# control.net
KiCad netlist of a schematic drawn in EAGLE
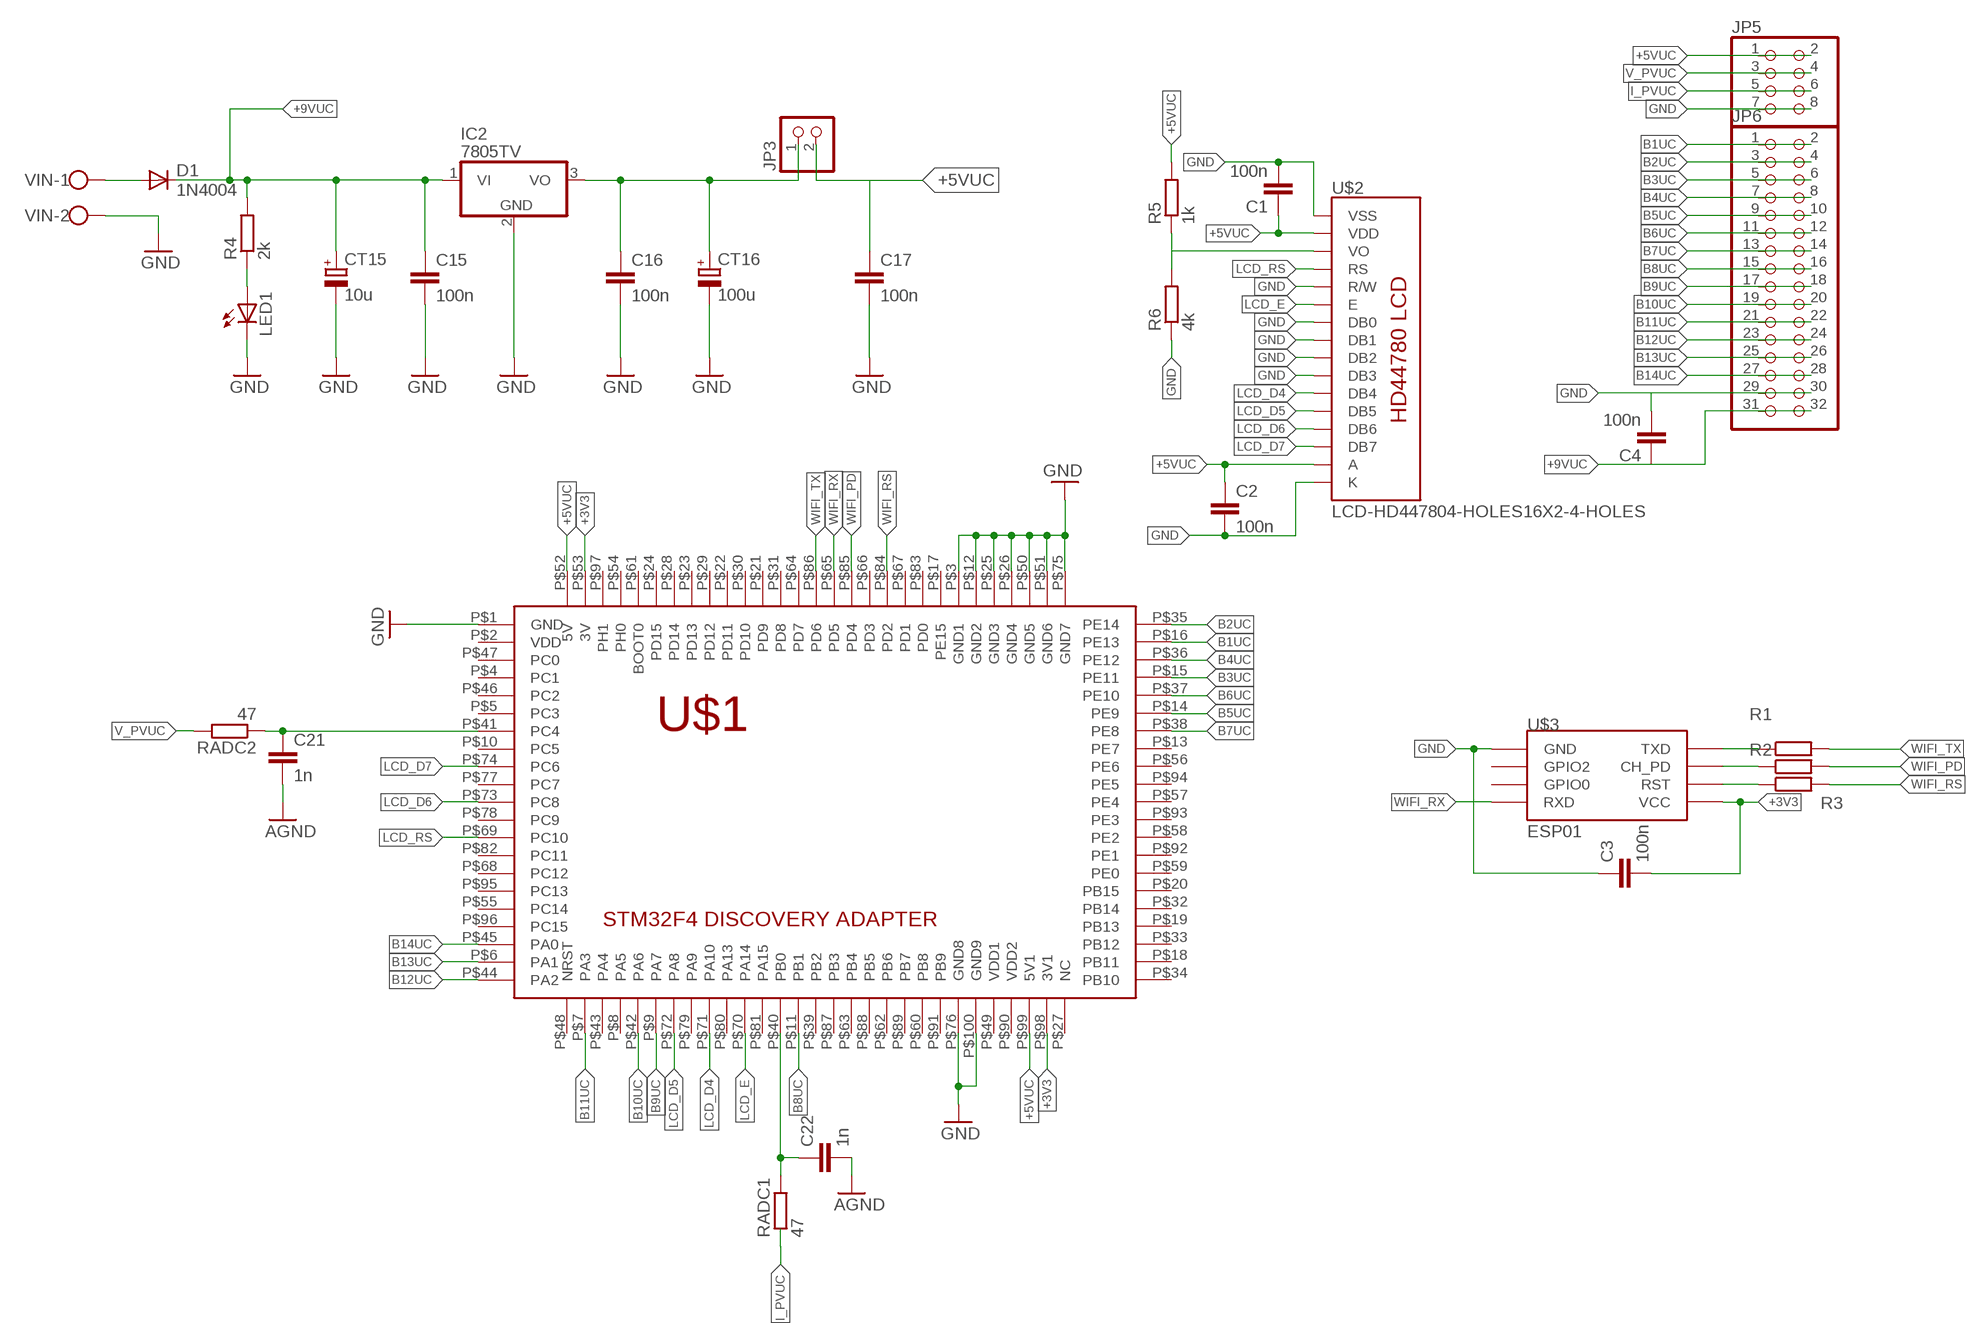
[diagram p0: schematic, sheet 1]

(export (version "E")
  (design (tool "Eeschema 10.0.6"))
  (components
    (comp (ref "C1")
      (value "100n")
      (footprint "eagle-import:C1206")
      (libsource (lib "eagle-import") (part "C-EUC1206"))
    )
    (comp (ref "C2")
      (value "100n")
      (footprint "eagle-import:C1206")
      (libsource (lib "eagle-import") (part "C-EUC1206"))
    )
    (comp (ref "C3")
      (value "100n")
      (footprint "eagle-import:C1206")
      (libsource (lib "eagle-import") (part "C-EUC1206"))
    )
    (comp (ref "C4")
      (value "100n")
      (footprint "eagle-import:C1206")
      (libsource (lib "eagle-import") (part "C-EUC1206"))
    )
    (comp (ref "C15")
      (value "100n")
      (footprint "eagle-import:C1206")
      (libsource (lib "eagle-import") (part "C-EUC1206"))
    )
    (comp (ref "C16")
      (value "100n")
      (footprint "eagle-import:C1206")
      (libsource (lib "eagle-import") (part "C-EUC1206"))
    )
    (comp (ref "C17")
      (value "100n")
      (footprint "eagle-import:C1206")
      (libsource (lib "eagle-import") (part "C-EUC1206"))
    )
    (comp (ref "C21")
      (value "1n")
      (footprint "eagle-import:C1206")
      (libsource (lib "eagle-import") (part "C-EUC1206"))
    )
    (comp (ref "C22")
      (value "1n")
      (footprint "eagle-import:C1206")
      (libsource (lib "eagle-import") (part "C-EUC1206"))
    )
    (comp (ref "CT15")
      (value "10u")
      (footprint "eagle-import:B_3528-21W")
      (libsource (lib "eagle-import") (part "CPOL-EUB/3528-21W"))
    )
    (comp (ref "CT16")
      (value "100u")
      (footprint "eagle-import:D_7343-31R")
      (libsource (lib "eagle-import") (part "CPOL-EUD/7343-31R"))
    )
    (comp (ref "D1")
      (value "1N4004")
      (footprint "eagle-import:DO214AC")
      (libsource (lib "eagle-import") (part "1N4004"))
    )
    (comp (ref "IC2")
      (value "7805TV")
      (footprint "eagle-import:TO220V")
      (libsource (lib "eagle-import") (part "78TV05"))
    )
    (comp (ref "JP3")
      (value "PINHD-1X2")
      (footprint "eagle-import:1X02")
      (libsource (lib "eagle-import") (part "PINHD-1X2"))
    )
    (comp (ref "JP5")
      (value "PINHD-2X4/90")
      (footprint "eagle-import:2X04_90")
      (libsource (lib "eagle-import") (part "PINHD-2X4/90"))
    )
    (comp (ref "JP6")
      (value "PINHD-2X16/90")
      (footprint "eagle-import:2X16_90")
      (libsource (lib "eagle-import") (part "PINHD-2X16/90"))
    )
    (comp (ref "LED1")
      (value "LEDCHIPLED_0805")
      (footprint "eagle-import:CHIPLED_0805")
      (libsource (lib "eagle-import") (part "LEDCHIPLED_0805"))
    )
    (comp (ref "R1")
      (value "R-EU_R0603")
      (footprint "eagle-import:R0603")
      (libsource (lib "eagle-import") (part "R-EU_R0603"))
    )
    (comp (ref "R2")
      (value "R-EU_R0603")
      (footprint "eagle-import:R0603")
      (libsource (lib "eagle-import") (part "R-EU_R0603"))
    )
    (comp (ref "R3")
      (value "R-EU_R0603")
      (footprint "eagle-import:R0603")
      (libsource (lib "eagle-import") (part "R-EU_R0603"))
    )
    (comp (ref "R4")
      (value "2k")
      (footprint "eagle-import:M1206")
      (libsource (lib "eagle-import") (part "R-EU_M1206"))
    )
    (comp (ref "R5")
      (value "1k")
      (footprint "eagle-import:M1206")
      (libsource (lib "eagle-import") (part "R-EU_M1206"))
    )
    (comp (ref "R6")
      (value "4k")
      (footprint "eagle-import:M1206")
      (libsource (lib "eagle-import") (part "R-EU_M1206"))
    )
    (comp (ref "RADC1")
      (value "47")
      (footprint "eagle-import:R1206")
      (libsource (lib "eagle-import") (part "R-EU_R1206"))
    )
    (comp (ref "RADC2")
      (value "47")
      (footprint "eagle-import:R1206")
      (libsource (lib "eagle-import") (part "R-EU_R1206"))
    )
    (comp (ref "U$1")
      (value "STM32F4ADAPTER")
      (footprint "eagle-import:DISCOVERYPACK")
      (libsource (lib "eagle-import") (part "STM32F4ADAPTER"))
    )
    (comp (ref "U$2")
      (value "LCD-HD447804-HOLES16X2-4-HOLES")
      (footprint "eagle-import:LCD-16X2-4HOLES")
      (libsource (lib "eagle-import") (part "LCD-HD4478016X2-4-HOLES4-HOLES"))
    )
    (comp (ref "U$3")
      (value "ESP01")
      (footprint "eagle-import:ESP01")
      (libsource (lib "eagle-import") (part "ESP01"))
    )
    (comp (ref "VIN")
      (value "W237-102")
      (footprint "eagle-import:W237-102")
      (fields (field (name "MPN") "237-102"))
      (libsource (lib "eagle-import") (part "W237-102"))
    )
  )
  (nets
    (net (code "1") (name "+3V3") (class "Default")
      (node (ref "C3") (pin "2") (pinfunction "2_2") (pintype "passive"))
      (node (ref "U$1") (pin "P$53") (pinfunction "3V_P$53") (pintype "bidirectional"))
      (node (ref "U$1") (pin "P$98") (pinfunction "3V1_P$98") (pintype "bidirectional"))
      (node (ref "U$3") (pin "VCC") (pinfunction "VCC_VCC") (pintype "bidirectional"))
    )
    (net (code "2") (name "+5VUC") (class "Default")
      (node (ref "C1") (pin "1") (pinfunction "1_1") (pintype "passive"))
      (node (ref "C17") (pin "1") (pinfunction "1_1") (pintype "passive"))
      (node (ref "C2") (pin "1") (pinfunction "1_1") (pintype "passive"))
      (node (ref "JP3") (pin "2") (pinfunction "2_2") (pintype "passive"))
      (node (ref "JP5") (pin "1") (pinfunction "1_1") (pintype "passive"))
      (node (ref "JP5") (pin "2") (pinfunction "2_2") (pintype "passive"))
      (node (ref "R5") (pin "2") (pinfunction "2_2") (pintype "passive"))
      (node (ref "U$1") (pin "P$52") (pinfunction "5V_P$52") (pintype "bidirectional"))
      (node (ref "U$1") (pin "P$99") (pinfunction "5V1_P$99") (pintype "bidirectional"))
      (node (ref "U$2") (pin "15") (pinfunction "A_15") (pintype "power_in"))
      (node (ref "U$2") (pin "2") (pinfunction "VDD_2") (pintype "power_in"))
    )
    (net (code "3") (name "+9VUC") (class "Default")
      (node (ref "C15") (pin "1") (pinfunction "1_1") (pintype "passive"))
      (node (ref "C4") (pin "1") (pinfunction "1_1") (pintype "passive"))
      (node (ref "CT15") (pin "+") (pinfunction "+_+") (pintype "passive"))
      (node (ref "D1") (pin "C") (pinfunction "C_C") (pintype "passive"))
      (node (ref "IC2") (pin "1") (pinfunction "VI_1") (pintype "input"))
      (node (ref "JP6") (pin "31") (pinfunction "31_31") (pintype "passive"))
      (node (ref "JP6") (pin "32") (pinfunction "32_32") (pintype "passive"))
      (node (ref "R4") (pin "2") (pinfunction "2_2") (pintype "passive"))
    )
    (net (code "4") (name "B1UC") (class "Default")
      (node (ref "JP6") (pin "1") (pinfunction "1_1") (pintype "passive"))
      (node (ref "JP6") (pin "2") (pinfunction "2_2") (pintype "passive"))
      (node (ref "U$1") (pin "P$16") (pinfunction "PE13_P$16") (pintype "bidirectional"))
    )
    (net (code "5") (name "B2UC") (class "Default")
      (node (ref "JP6") (pin "3") (pinfunction "3_3") (pintype "passive"))
      (node (ref "JP6") (pin "4") (pinfunction "4_4") (pintype "passive"))
      (node (ref "U$1") (pin "P$35") (pinfunction "PE14_P$35") (pintype "bidirectional"))
    )
    (net (code "6") (name "B3UC") (class "Default")
      (node (ref "JP6") (pin "5") (pinfunction "5_5") (pintype "passive"))
      (node (ref "JP6") (pin "6") (pinfunction "6_6") (pintype "passive"))
      (node (ref "U$1") (pin "P$15") (pinfunction "PE11_P$15") (pintype "bidirectional"))
    )
    (net (code "7") (name "B4UC") (class "Default")
      (node (ref "JP6") (pin "7") (pinfunction "7_7") (pintype "passive"))
      (node (ref "JP6") (pin "8") (pinfunction "8_8") (pintype "passive"))
      (node (ref "U$1") (pin "P$36") (pinfunction "PE12_P$36") (pintype "bidirectional"))
    )
    (net (code "8") (name "B5UC") (class "Default")
      (node (ref "JP6") (pin "10") (pinfunction "10_10") (pintype "passive"))
      (node (ref "JP6") (pin "9") (pinfunction "9_9") (pintype "passive"))
      (node (ref "U$1") (pin "P$14") (pinfunction "PE9_P$14") (pintype "bidirectional"))
    )
    (net (code "9") (name "B6UC") (class "Default")
      (node (ref "JP6") (pin "11") (pinfunction "11_11") (pintype "passive"))
      (node (ref "JP6") (pin "12") (pinfunction "12_12") (pintype "passive"))
      (node (ref "U$1") (pin "P$37") (pinfunction "PE10_P$37") (pintype "bidirectional"))
    )
    (net (code "10") (name "B7UC") (class "Default")
      (node (ref "JP6") (pin "13") (pinfunction "13_13") (pintype "passive"))
      (node (ref "JP6") (pin "14") (pinfunction "14_14") (pintype "passive"))
      (node (ref "U$1") (pin "P$38") (pinfunction "PE8_P$38") (pintype "bidirectional"))
    )
    (net (code "11") (name "B8UC") (class "Default")
      (node (ref "JP6") (pin "15") (pinfunction "15_15") (pintype "passive"))
      (node (ref "JP6") (pin "16") (pinfunction "16_16") (pintype "passive"))
      (node (ref "U$1") (pin "P$11") (pinfunction "PB1_P$11") (pintype "bidirectional"))
    )
    (net (code "12") (name "B9UC") (class "Default")
      (node (ref "JP6") (pin "17") (pinfunction "17_17") (pintype "passive"))
      (node (ref "JP6") (pin "18") (pinfunction "18_18") (pintype "passive"))
      (node (ref "U$1") (pin "P$9") (pinfunction "PA7_P$9") (pintype "bidirectional"))
    )
    (net (code "13") (name "B10UC") (class "Default")
      (node (ref "JP6") (pin "19") (pinfunction "19_19") (pintype "passive"))
      (node (ref "JP6") (pin "20") (pinfunction "20_20") (pintype "passive"))
      (node (ref "U$1") (pin "P$42") (pinfunction "PA6_P$42") (pintype "bidirectional"))
    )
    (net (code "14") (name "B11UC") (class "Default")
      (node (ref "JP6") (pin "21") (pinfunction "21_21") (pintype "passive"))
      (node (ref "JP6") (pin "22") (pinfunction "22_22") (pintype "passive"))
      (node (ref "U$1") (pin "P$7") (pinfunction "PA3_P$7") (pintype "bidirectional"))
    )
    (net (code "15") (name "B12UC") (class "Default")
      (node (ref "JP6") (pin "23") (pinfunction "23_23") (pintype "passive"))
      (node (ref "JP6") (pin "24") (pinfunction "24_24") (pintype "passive"))
      (node (ref "U$1") (pin "P$44") (pinfunction "PA2_P$44") (pintype "bidirectional"))
    )
    (net (code "16") (name "B13UC") (class "Default")
      (node (ref "JP6") (pin "25") (pinfunction "25_25") (pintype "passive"))
      (node (ref "JP6") (pin "26") (pinfunction "26_26") (pintype "passive"))
      (node (ref "U$1") (pin "P$6") (pinfunction "PA1_P$6") (pintype "bidirectional"))
    )
    (net (code "17") (name "B14UC") (class "Default")
      (node (ref "JP6") (pin "27") (pinfunction "27_27") (pintype "passive"))
      (node (ref "JP6") (pin "28") (pinfunction "28_28") (pintype "passive"))
      (node (ref "U$1") (pin "P$45") (pinfunction "PA0_P$45") (pintype "bidirectional"))
    )
    (net (code "18") (name "GND") (class "Default")
      (node (ref "C1") (pin "2") (pinfunction "2_2") (pintype "passive"))
      (node (ref "C15") (pin "2") (pinfunction "2_2") (pintype "passive"))
      (node (ref "C16") (pin "2") (pinfunction "2_2") (pintype "passive"))
      (node (ref "C17") (pin "2") (pinfunction "2_2") (pintype "passive"))
      (node (ref "C2") (pin "2") (pinfunction "2_2") (pintype "passive"))
      (node (ref "C21") (pin "2") (pinfunction "2_2") (pintype "passive"))
      (node (ref "C22") (pin "2") (pinfunction "2_2") (pintype "passive"))
      (node (ref "C3") (pin "1") (pinfunction "1_1") (pintype "passive"))
      (node (ref "C4") (pin "2") (pinfunction "2_2") (pintype "passive"))
      (node (ref "CT15") (pin "-") (pinfunction "-_-") (pintype "passive"))
      (node (ref "CT16") (pin "-") (pinfunction "-_-") (pintype "passive"))
      (node (ref "IC2") (pin "2") (pinfunction "GND_2") (pintype "passive"))
      (node (ref "JP5") (pin "7") (pinfunction "7_7") (pintype "passive"))
      (node (ref "JP5") (pin "8") (pinfunction "8_8") (pintype "passive"))
      (node (ref "JP6") (pin "29") (pinfunction "29_29") (pintype "passive"))
      (node (ref "JP6") (pin "30") (pinfunction "30_30") (pintype "passive"))
      (node (ref "LED1") (pin "C") (pinfunction "C_C") (pintype "passive"))
      (node (ref "R6") (pin "1") (pinfunction "1_1") (pintype "passive"))
      (node (ref "U$1") (pin "P$1") (pinfunction "GND_P$1") (pintype "bidirectional"))
      (node (ref "U$1") (pin "P$100") (pinfunction "GND9_P$100") (pintype "bidirectional"))
      (node (ref "U$1") (pin "P$12") (pinfunction "GND2_P$12") (pintype "bidirectional"))
      (node (ref "U$1") (pin "P$25") (pinfunction "GND3_P$25") (pintype "bidirectional"))
      (node (ref "U$1") (pin "P$26") (pinfunction "GND4_P$26") (pintype "bidirectional"))
      (node (ref "U$1") (pin "P$3") (pinfunction "GND1_P$3") (pintype "bidirectional"))
      (node (ref "U$1") (pin "P$50") (pinfunction "GND5_P$50") (pintype "bidirectional"))
      (node (ref "U$1") (pin "P$51") (pinfunction "GND6_P$51") (pintype "bidirectional"))
      (node (ref "U$1") (pin "P$75") (pinfunction "GND7_P$75") (pintype "bidirectional"))
      (node (ref "U$1") (pin "P$76") (pinfunction "GND8_P$76") (pintype "bidirectional"))
      (node (ref "U$2") (pin "1") (pinfunction "VSS_1") (pintype "power_in"))
      (node (ref "U$2") (pin "10") (pinfunction "DB3_10") (pintype "bidirectional"))
      (node (ref "U$2") (pin "16") (pinfunction "K_16") (pintype "power_in"))
      (node (ref "U$2") (pin "5") (pinfunction "R/W_5") (pintype "input"))
      (node (ref "U$2") (pin "7") (pinfunction "DB0_7") (pintype "bidirectional"))
      (node (ref "U$2") (pin "8") (pinfunction "DB1_8") (pintype "bidirectional"))
      (node (ref "U$2") (pin "9") (pinfunction "DB2_9") (pintype "bidirectional"))
      (node (ref "U$3") (pin "GND") (pinfunction "GND_GND") (pintype "bidirectional"))
      (node (ref "VIN") (pin "2") (pinfunction "KL_2") (pintype "passive"))
    )
    (net (code "19") (name "I_PVUC") (class "Default")
      (node (ref "JP5") (pin "5") (pinfunction "5_5") (pintype "passive"))
      (node (ref "JP5") (pin "6") (pinfunction "6_6") (pintype "passive"))
      (node (ref "RADC1") (pin "1") (pinfunction "1_1") (pintype "passive"))
    )
    (net (code "20") (name "LCD_D4") (class "Default")
      (node (ref "U$1") (pin "P$71") (pinfunction "PA10_P$71") (pintype "bidirectional"))
      (node (ref "U$2") (pin "11") (pinfunction "DB4_11") (pintype "bidirectional"))
    )
    (net (code "21") (name "LCD_D5") (class "Default")
      (node (ref "U$1") (pin "P$72") (pinfunction "PA8_P$72") (pintype "bidirectional"))
      (node (ref "U$2") (pin "12") (pinfunction "DB5_12") (pintype "bidirectional"))
    )
    (net (code "22") (name "LCD_D6") (class "Default")
      (node (ref "U$1") (pin "P$73") (pinfunction "PC8_P$73") (pintype "bidirectional"))
      (node (ref "U$2") (pin "13") (pinfunction "DB6_13") (pintype "bidirectional"))
    )
    (net (code "23") (name "LCD_D7") (class "Default")
      (node (ref "U$1") (pin "P$74") (pinfunction "PC6_P$74") (pintype "bidirectional"))
      (node (ref "U$2") (pin "14") (pinfunction "DB7_14") (pintype "bidirectional"))
    )
    (net (code "24") (name "LCD_E") (class "Default")
      (node (ref "U$1") (pin "P$70") (pinfunction "PA14_P$70") (pintype "bidirectional"))
      (node (ref "U$2") (pin "6") (pinfunction "E_6") (pintype "input"))
    )
    (net (code "25") (name "LCD_RS") (class "Default")
      (node (ref "U$1") (pin "P$69") (pinfunction "PC10_P$69") (pintype "bidirectional"))
      (node (ref "U$2") (pin "4") (pinfunction "RS_4") (pintype "input"))
    )
    (net (code "26") (name "Net-(IC2-VO)") (class "Default")
      (node (ref "C16") (pin "1") (pinfunction "1_1") (pintype "passive"))
      (node (ref "CT16") (pin "+") (pinfunction "+_+") (pintype "passive"))
      (node (ref "IC2") (pin "3") (pinfunction "VO_3") (pintype "passive"))
      (node (ref "JP3") (pin "1") (pinfunction "1_1") (pintype "passive"))
    )
    (net (code "27") (name "Net-(LED1-PadA)") (class "Default")
      (node (ref "LED1") (pin "A") (pinfunction "A_A") (pintype "passive"))
      (node (ref "R4") (pin "1") (pinfunction "1_1") (pintype "passive"))
    )
    (net (code "28") (name "Net-(R2-Pad1)") (class "Default")
      (node (ref "R2") (pin "1") (pinfunction "1_1") (pintype "passive"))
      (node (ref "U$3") (pin "CH_PD") (pinfunction "CH_PD_CH_PD") (pintype "bidirectional"))
    )
    (net (code "29") (name "Net-(R3-Pad1)") (class "Default")
      (node (ref "R3") (pin "1") (pinfunction "1_1") (pintype "passive"))
      (node (ref "U$3") (pin "RST") (pinfunction "RST_RST") (pintype "bidirectional"))
    )
    (net (code "30") (name "Net-(U$1-PB0)") (class "Default")
      (node (ref "C22") (pin "1") (pinfunction "1_1") (pintype "passive"))
      (node (ref "RADC1") (pin "2") (pinfunction "2_2") (pintype "passive"))
      (node (ref "U$1") (pin "P$40") (pinfunction "PB0_P$40") (pintype "bidirectional"))
    )
    (net (code "31") (name "Net-(U$1-PC4)") (class "Default")
      (node (ref "C21") (pin "1") (pinfunction "1_1") (pintype "passive"))
      (node (ref "RADC2") (pin "1") (pinfunction "1_1") (pintype "passive"))
      (node (ref "U$1") (pin "P$41") (pinfunction "PC4_P$41") (pintype "bidirectional"))
    )
    (net (code "32") (name "Net-(U$2-VO)") (class "Default")
      (node (ref "R5") (pin "1") (pinfunction "1_1") (pintype "passive"))
      (node (ref "R6") (pin "2") (pinfunction "2_2") (pintype "passive"))
      (node (ref "U$2") (pin "3") (pinfunction "VO_3") (pintype "bidirectional"))
    )
    (net (code "33") (name "Net-(U$3-TXD)") (class "Default")
      (node (ref "R1") (pin "1") (pinfunction "1_1") (pintype "passive"))
      (node (ref "U$3") (pin "TX") (pinfunction "TXD_TX") (pintype "bidirectional"))
    )
    (net (code "34") (name "Net-(VINA-KL)") (class "Default")
      (node (ref "D1") (pin "A") (pinfunction "A_A") (pintype "passive"))
      (node (ref "VIN") (pin "1") (pinfunction "KL_1") (pintype "passive"))
    )
    (net (code "35") (name "V_PVUC") (class "Default")
      (node (ref "JP5") (pin "3") (pinfunction "3_3") (pintype "passive"))
      (node (ref "JP5") (pin "4") (pinfunction "4_4") (pintype "passive"))
      (node (ref "RADC2") (pin "2") (pinfunction "2_2") (pintype "passive"))
    )
    (net (code "36") (name "WIFI_PD") (class "Default")
      (node (ref "R2") (pin "2") (pinfunction "2_2") (pintype "passive"))
      (node (ref "U$1") (pin "P$85") (pinfunction "PD4_P$85") (pintype "bidirectional"))
    )
    (net (code "37") (name "WIFI_RS") (class "Default")
      (node (ref "R3") (pin "2") (pinfunction "2_2") (pintype "passive"))
      (node (ref "U$1") (pin "P$84") (pinfunction "PD2_P$84") (pintype "bidirectional"))
    )
    (net (code "38") (name "WIFI_RX") (class "Default")
      (node (ref "U$1") (pin "P$65") (pinfunction "PD5_P$65") (pintype "bidirectional"))
      (node (ref "U$3") (pin "RX") (pinfunction "RXD_RX") (pintype "bidirectional"))
    )
    (net (code "39") (name "WIFI_TX") (class "Default")
      (node (ref "R1") (pin "2") (pinfunction "2_2") (pintype "passive"))
      (node (ref "U$1") (pin "P$86") (pinfunction "PD6_P$86") (pintype "bidirectional"))
    )
    (net (code "40") (name "unconnected-(U$1-BOOT0-PadP$61)") (class "Default")
      (node (ref "U$1") (pin "P$61") (pinfunction "BOOT0_P$61") (pintype "bidirectional"))
    )
    (net (code "41") (name "unconnected-(U$1-NC-PadP$27)") (class "Default")
      (node (ref "U$1") (pin "P$27") (pinfunction "NC_P$27") (pintype "bidirectional"))
    )
    (net (code "42") (name "unconnected-(U$1-NRST-PadP$48)") (class "Default")
      (node (ref "U$1") (pin "P$48") (pinfunction "NRST_P$48") (pintype "bidirectional"))
    )
    (net (code "43") (name "unconnected-(U$1-PA4-PadP$43)") (class "Default")
      (node (ref "U$1") (pin "P$43") (pinfunction "PA4_P$43") (pintype "bidirectional"))
    )
    (net (code "44") (name "unconnected-(U$1-PA5-PadP$8)") (class "Default")
      (node (ref "U$1") (pin "P$8") (pinfunction "PA5_P$8") (pintype "bidirectional"))
    )
    (net (code "45") (name "unconnected-(U$1-PA9-PadP$79)") (class "Default")
      (node (ref "U$1") (pin "P$79") (pinfunction "PA9_P$79") (pintype "bidirectional"))
    )
    (net (code "46") (name "unconnected-(U$1-PA13-PadP$80)") (class "Default")
      (node (ref "U$1") (pin "P$80") (pinfunction "PA13_P$80") (pintype "bidirectional"))
    )
    (net (code "47") (name "unconnected-(U$1-PA15-PadP$81)") (class "Default")
      (node (ref "U$1") (pin "P$81") (pinfunction "PA15_P$81") (pintype "bidirectional"))
    )
    (net (code "48") (name "unconnected-(U$1-PB2-PadP$39)") (class "Default")
      (node (ref "U$1") (pin "P$39") (pinfunction "PB2_P$39") (pintype "bidirectional"))
    )
    (net (code "49") (name "unconnected-(U$1-PB3-PadP$87)") (class "Default")
      (node (ref "U$1") (pin "P$87") (pinfunction "PB3_P$87") (pintype "bidirectional"))
    )
    (net (code "50") (name "unconnected-(U$1-PB4-PadP$63)") (class "Default")
      (node (ref "U$1") (pin "P$63") (pinfunction "PB4_P$63") (pintype "bidirectional"))
    )
    (net (code "51") (name "unconnected-(U$1-PB5-PadP$88)") (class "Default")
      (node (ref "U$1") (pin "P$88") (pinfunction "PB5_P$88") (pintype "bidirectional"))
    )
    (net (code "52") (name "unconnected-(U$1-PB6-PadP$62)") (class "Default")
      (node (ref "U$1") (pin "P$62") (pinfunction "PB6_P$62") (pintype "bidirectional"))
    )
    (net (code "53") (name "unconnected-(U$1-PB7-PadP$89)") (class "Default")
      (node (ref "U$1") (pin "P$89") (pinfunction "PB7_P$89") (pintype "bidirectional"))
    )
    (net (code "54") (name "unconnected-(U$1-PB8-PadP$60)") (class "Default")
      (node (ref "U$1") (pin "P$60") (pinfunction "PB8_P$60") (pintype "bidirectional"))
    )
    (net (code "55") (name "unconnected-(U$1-PB9-PadP$91)") (class "Default")
      (node (ref "U$1") (pin "P$91") (pinfunction "PB9_P$91") (pintype "bidirectional"))
    )
    (net (code "56") (name "unconnected-(U$1-PB10-PadP$34)") (class "Default")
      (node (ref "U$1") (pin "P$34") (pinfunction "PB10_P$34") (pintype "bidirectional"))
    )
    (net (code "57") (name "unconnected-(U$1-PB11-PadP$18)") (class "Default")
      (node (ref "U$1") (pin "P$18") (pinfunction "PB11_P$18") (pintype "bidirectional"))
    )
    (net (code "58") (name "unconnected-(U$1-PB12-PadP$33)") (class "Default")
      (node (ref "U$1") (pin "P$33") (pinfunction "PB12_P$33") (pintype "bidirectional"))
    )
    (net (code "59") (name "unconnected-(U$1-PB13-PadP$19)") (class "Default")
      (node (ref "U$1") (pin "P$19") (pinfunction "PB13_P$19") (pintype "bidirectional"))
    )
    (net (code "60") (name "unconnected-(U$1-PB14-PadP$32)") (class "Default")
      (node (ref "U$1") (pin "P$32") (pinfunction "PB14_P$32") (pintype "bidirectional"))
    )
    (net (code "61") (name "unconnected-(U$1-PB15-PadP$20)") (class "Default")
      (node (ref "U$1") (pin "P$20") (pinfunction "PB15_P$20") (pintype "bidirectional"))
    )
    (net (code "62") (name "unconnected-(U$1-PC0-PadP$47)") (class "Default")
      (node (ref "U$1") (pin "P$47") (pinfunction "PC0_P$47") (pintype "bidirectional"))
    )
    (net (code "63") (name "unconnected-(U$1-PC1-PadP$4)") (class "Default")
      (node (ref "U$1") (pin "P$4") (pinfunction "PC1_P$4") (pintype "bidirectional"))
    )
    (net (code "64") (name "unconnected-(U$1-PC2-PadP$46)") (class "Default")
      (node (ref "U$1") (pin "P$46") (pinfunction "PC2_P$46") (pintype "bidirectional"))
    )
    (net (code "65") (name "unconnected-(U$1-PC3-PadP$5)") (class "Default")
      (node (ref "U$1") (pin "P$5") (pinfunction "PC3_P$5") (pintype "bidirectional"))
    )
    (net (code "66") (name "unconnected-(U$1-PC5-PadP$10)") (class "Default")
      (node (ref "U$1") (pin "P$10") (pinfunction "PC5_P$10") (pintype "bidirectional"))
    )
    (net (code "67") (name "unconnected-(U$1-PC7-PadP$77)") (class "Default")
      (node (ref "U$1") (pin "P$77") (pinfunction "PC7_P$77") (pintype "bidirectional"))
    )
    (net (code "68") (name "unconnected-(U$1-PC9-PadP$78)") (class "Default")
      (node (ref "U$1") (pin "P$78") (pinfunction "PC9_P$78") (pintype "bidirectional"))
    )
    (net (code "69") (name "unconnected-(U$1-PC11-PadP$82)") (class "Default")
      (node (ref "U$1") (pin "P$82") (pinfunction "PC11_P$82") (pintype "bidirectional"))
    )
    (net (code "70") (name "unconnected-(U$1-PC12-PadP$68)") (class "Default")
      (node (ref "U$1") (pin "P$68") (pinfunction "PC12_P$68") (pintype "bidirectional"))
    )
    (net (code "71") (name "unconnected-(U$1-PC13-PadP$95)") (class "Default")
      (node (ref "U$1") (pin "P$95") (pinfunction "PC13_P$95") (pintype "bidirectional"))
    )
    (net (code "72") (name "unconnected-(U$1-PC14-PadP$55)") (class "Default")
      (node (ref "U$1") (pin "P$55") (pinfunction "PC14_P$55") (pintype "bidirectional"))
    )
    (net (code "73") (name "unconnected-(U$1-PC15-PadP$96)") (class "Default")
      (node (ref "U$1") (pin "P$96") (pinfunction "PC15_P$96") (pintype "bidirectional"))
    )
    (net (code "74") (name "unconnected-(U$1-PD0-PadP$83)") (class "Default")
      (node (ref "U$1") (pin "P$83") (pinfunction "PD0_P$83") (pintype "bidirectional"))
    )
    (net (code "75") (name "unconnected-(U$1-PD1-PadP$67)") (class "Default")
      (node (ref "U$1") (pin "P$67") (pinfunction "PD1_P$67") (pintype "bidirectional"))
    )
    (net (code "76") (name "unconnected-(U$1-PD3-PadP$66)") (class "Default")
      (node (ref "U$1") (pin "P$66") (pinfunction "PD3_P$66") (pintype "bidirectional"))
    )
    (net (code "77") (name "unconnected-(U$1-PD7-PadP$64)") (class "Default")
      (node (ref "U$1") (pin "P$64") (pinfunction "PD7_P$64") (pintype "bidirectional"))
    )
    (net (code "78") (name "unconnected-(U$1-PD8-PadP$31)") (class "Default")
      (node (ref "U$1") (pin "P$31") (pinfunction "PD8_P$31") (pintype "bidirectional"))
    )
    (net (code "79") (name "unconnected-(U$1-PD9-PadP$21)") (class "Default")
      (node (ref "U$1") (pin "P$21") (pinfunction "PD9_P$21") (pintype "bidirectional"))
    )
    (net (code "80") (name "unconnected-(U$1-PD10-PadP$30)") (class "Default")
      (node (ref "U$1") (pin "P$30") (pinfunction "PD10_P$30") (pintype "bidirectional"))
    )
    (net (code "81") (name "unconnected-(U$1-PD11-PadP$22)") (class "Default")
      (node (ref "U$1") (pin "P$22") (pinfunction "PD11_P$22") (pintype "bidirectional"))
    )
    (net (code "82") (name "unconnected-(U$1-PD12-PadP$29)") (class "Default")
      (node (ref "U$1") (pin "P$29") (pinfunction "PD12_P$29") (pintype "bidirectional"))
    )
    (net (code "83") (name "unconnected-(U$1-PD13-PadP$23)") (class "Default")
      (node (ref "U$1") (pin "P$23") (pinfunction "PD13_P$23") (pintype "bidirectional"))
    )
    (net (code "84") (name "unconnected-(U$1-PD14-PadP$28)") (class "Default")
      (node (ref "U$1") (pin "P$28") (pinfunction "PD14_P$28") (pintype "bidirectional"))
    )
    (net (code "85") (name "unconnected-(U$1-PD15-PadP$24)") (class "Default")
      (node (ref "U$1") (pin "P$24") (pinfunction "PD15_P$24") (pintype "bidirectional"))
    )
    (net (code "86") (name "unconnected-(U$1-PE0-PadP$59)") (class "Default")
      (node (ref "U$1") (pin "P$59") (pinfunction "PE0_P$59") (pintype "bidirectional"))
    )
    (net (code "87") (name "unconnected-(U$1-PE1-PadP$92)") (class "Default")
      (node (ref "U$1") (pin "P$92") (pinfunction "PE1_P$92") (pintype "bidirectional"))
    )
    (net (code "88") (name "unconnected-(U$1-PE2-PadP$58)") (class "Default")
      (node (ref "U$1") (pin "P$58") (pinfunction "PE2_P$58") (pintype "bidirectional"))
    )
    (net (code "89") (name "unconnected-(U$1-PE3-PadP$93)") (class "Default")
      (node (ref "U$1") (pin "P$93") (pinfunction "PE3_P$93") (pintype "bidirectional"))
    )
    (net (code "90") (name "unconnected-(U$1-PE4-PadP$57)") (class "Default")
      (node (ref "U$1") (pin "P$57") (pinfunction "PE4_P$57") (pintype "bidirectional"))
    )
    (net (code "91") (name "unconnected-(U$1-PE5-PadP$94)") (class "Default")
      (node (ref "U$1") (pin "P$94") (pinfunction "PE5_P$94") (pintype "bidirectional"))
    )
    (net (code "92") (name "unconnected-(U$1-PE6-PadP$56)") (class "Default")
      (node (ref "U$1") (pin "P$56") (pinfunction "PE6_P$56") (pintype "bidirectional"))
    )
    (net (code "93") (name "unconnected-(U$1-PE7-PadP$13)") (class "Default")
      (node (ref "U$1") (pin "P$13") (pinfunction "PE7_P$13") (pintype "bidirectional"))
    )
    (net (code "94") (name "unconnected-(U$1-PE15-PadP$17)") (class "Default")
      (node (ref "U$1") (pin "P$17") (pinfunction "PE15_P$17") (pintype "bidirectional"))
    )
    (net (code "95") (name "unconnected-(U$1-PH0-PadP$54)") (class "Default")
      (node (ref "U$1") (pin "P$54") (pinfunction "PH0_P$54") (pintype "bidirectional"))
    )
    (net (code "96") (name "unconnected-(U$1-PH1-PadP$97)") (class "Default")
      (node (ref "U$1") (pin "P$97") (pinfunction "PH1_P$97") (pintype "bidirectional"))
    )
    (net (code "97") (name "unconnected-(U$1-VDD-PadP$2)") (class "Default")
      (node (ref "U$1") (pin "P$2") (pinfunction "VDD_P$2") (pintype "bidirectional"))
    )
    (net (code "98") (name "unconnected-(U$1-VDD1-PadP$49)") (class "Default")
      (node (ref "U$1") (pin "P$49") (pinfunction "VDD1_P$49") (pintype "bidirectional"))
    )
    (net (code "99") (name "unconnected-(U$1-VDD2-PadP$90)") (class "Default")
      (node (ref "U$1") (pin "P$90") (pinfunction "VDD2_P$90") (pintype "bidirectional"))
    )
    (net (code "100") (name "unconnected-(U$3-PadGPIO0)") (class "Default")
      (node (ref "U$3") (pin "GPIO0") (pinfunction "GPIO0_GPIO0") (pintype "bidirectional"))
    )
    (net (code "101") (name "unconnected-(U$3-PadGPIO2)") (class "Default")
      (node (ref "U$3") (pin "GPIO2") (pinfunction "GPIO2_GPIO2") (pintype "bidirectional"))
    )
  )
)
